# ornamentOrbV1.net
KiCad netlist of a schematic drawn in EAGLE
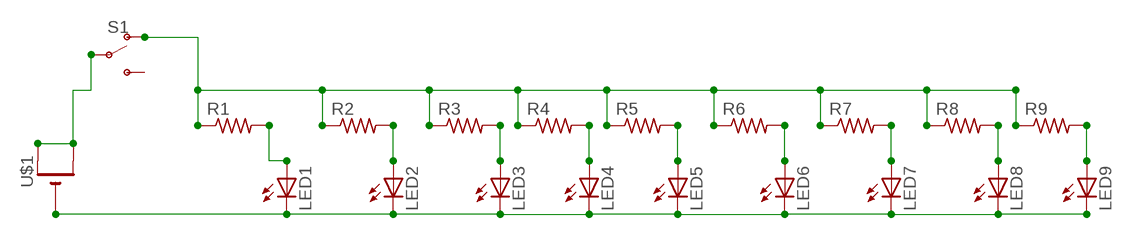
[diagram p0: schematic, sheet 1]

(export (version "E")
  (design (tool "Eeschema 10.0.6"))
  (components
    (comp (ref "LED1")
      (value "LED5MM")
      (footprint "eagle-import:LED5MM")
      (libsource (lib "eagle-import") (part "LED5MM"))
    )
    (comp (ref "LED2")
      (value "LED5MM")
      (footprint "eagle-import:LED5MM")
      (libsource (lib "eagle-import") (part "LED5MM"))
    )
    (comp (ref "LED3")
      (value "LED5MM")
      (footprint "eagle-import:LED5MM")
      (libsource (lib "eagle-import") (part "LED5MM"))
    )
    (comp (ref "LED4")
      (value "LED5MM")
      (footprint "eagle-import:LED5MM")
      (libsource (lib "eagle-import") (part "LED5MM"))
    )
    (comp (ref "LED5")
      (value "LED5MM")
      (footprint "eagle-import:LED5MM")
      (libsource (lib "eagle-import") (part "LED5MM"))
    )
    (comp (ref "LED6")
      (value "LED5MM")
      (footprint "eagle-import:LED5MM")
      (libsource (lib "eagle-import") (part "LED5MM"))
    )
    (comp (ref "LED7")
      (value "LED5MM")
      (footprint "eagle-import:LED5MM")
      (libsource (lib "eagle-import") (part "LED5MM"))
    )
    (comp (ref "LED8")
      (value "LED5MM")
      (footprint "eagle-import:LED5MM")
      (libsource (lib "eagle-import") (part "LED5MM"))
    )
    (comp (ref "LED9")
      (value "LED5MM")
      (footprint "eagle-import:LED5MM")
      (libsource (lib "eagle-import") (part "LED5MM"))
    )
    (comp (ref "R1")
      (value "R-US_R0805")
      (footprint "eagle-import:R0805")
      (libsource (lib "eagle-import") (part "R-US_R0805"))
    )
    (comp (ref "R2")
      (value "R-US_R0805")
      (footprint "eagle-import:R0805")
      (libsource (lib "eagle-import") (part "R-US_R0805"))
    )
    (comp (ref "R3")
      (value "R-US_R0805")
      (footprint "eagle-import:R0805")
      (libsource (lib "eagle-import") (part "R-US_R0805"))
    )
    (comp (ref "R4")
      (value "R-US_R0805")
      (footprint "eagle-import:R0805")
      (libsource (lib "eagle-import") (part "R-US_R0805"))
    )
    (comp (ref "R5")
      (value "R-US_R0805")
      (footprint "eagle-import:R0805")
      (libsource (lib "eagle-import") (part "R-US_R0805"))
    )
    (comp (ref "R6")
      (value "R-US_R0805")
      (footprint "eagle-import:R0805")
      (libsource (lib "eagle-import") (part "R-US_R0805"))
    )
    (comp (ref "R7")
      (value "R-US_R0805")
      (footprint "eagle-import:R0805")
      (libsource (lib "eagle-import") (part "R-US_R0805"))
    )
    (comp (ref "R8")
      (value "R-US_R0805")
      (footprint "eagle-import:R0805")
      (libsource (lib "eagle-import") (part "R-US_R0805"))
    )
    (comp (ref "R9")
      (value "R-US_R0805")
      (footprint "eagle-import:R0805")
      (libsource (lib "eagle-import") (part "R-US_R0805"))
    )
    (comp (ref "S1")
      (value "SWITCH-SPDT-SMD-RIGHT-ANGLE")
      (footprint "eagle-import:SWITCH_SPST_SMD_A")
      (libsource (lib "eagle-import") (part "SWITCH-SPDT-SMD-RIGHT-ANGLE"))
    )
    (comp (ref "U$1")
      (value "CR2032SMT")
      (footprint "eagle-import:CR2032-SMD")
      (libsource (lib "eagle-import") (part "CR2032SMT"))
    )
  )
  (nets
    (net (code "1") (name "Net-(LED1-C)") (class "Default")
      (node (ref "LED1") (pin "K") (pinfunction "C_K") (pintype "passive"))
      (node (ref "LED2") (pin "K") (pinfunction "C_K") (pintype "passive"))
      (node (ref "LED3") (pin "K") (pinfunction "C_K") (pintype "passive"))
      (node (ref "LED4") (pin "K") (pinfunction "C_K") (pintype "passive"))
      (node (ref "LED5") (pin "K") (pinfunction "C_K") (pintype "passive"))
      (node (ref "LED6") (pin "K") (pinfunction "C_K") (pintype "passive"))
      (node (ref "LED7") (pin "K") (pinfunction "C_K") (pintype "passive"))
      (node (ref "LED8") (pin "K") (pinfunction "C_K") (pintype "passive"))
      (node (ref "LED9") (pin "K") (pinfunction "C_K") (pintype "passive"))
      (node (ref "U$1") (pin "-") (pinfunction "-_-") (pintype "passive"))
    )
    (net (code "2") (name "Net-(LED1-PadA)") (class "Default")
      (node (ref "LED1") (pin "A") (pinfunction "A_A") (pintype "passive"))
      (node (ref "R1") (pin "2") (pinfunction "2_2") (pintype "passive"))
    )
    (net (code "3") (name "Net-(LED2-PadA)") (class "Default")
      (node (ref "LED2") (pin "A") (pinfunction "A_A") (pintype "passive"))
      (node (ref "R2") (pin "2") (pinfunction "2_2") (pintype "passive"))
    )
    (net (code "4") (name "Net-(LED3-PadA)") (class "Default")
      (node (ref "LED3") (pin "A") (pinfunction "A_A") (pintype "passive"))
      (node (ref "R3") (pin "2") (pinfunction "2_2") (pintype "passive"))
    )
    (net (code "5") (name "Net-(LED4-PadA)") (class "Default")
      (node (ref "LED4") (pin "A") (pinfunction "A_A") (pintype "passive"))
      (node (ref "R4") (pin "2") (pinfunction "2_2") (pintype "passive"))
    )
    (net (code "6") (name "Net-(LED5-PadA)") (class "Default")
      (node (ref "LED5") (pin "A") (pinfunction "A_A") (pintype "passive"))
      (node (ref "R5") (pin "2") (pinfunction "2_2") (pintype "passive"))
    )
    (net (code "7") (name "Net-(LED6-PadA)") (class "Default")
      (node (ref "LED6") (pin "A") (pinfunction "A_A") (pintype "passive"))
      (node (ref "R6") (pin "2") (pinfunction "2_2") (pintype "passive"))
    )
    (net (code "8") (name "Net-(LED7-PadA)") (class "Default")
      (node (ref "LED7") (pin "A") (pinfunction "A_A") (pintype "passive"))
      (node (ref "R7") (pin "2") (pinfunction "2_2") (pintype "passive"))
    )
    (net (code "9") (name "Net-(LED8-PadA)") (class "Default")
      (node (ref "LED8") (pin "A") (pinfunction "A_A") (pintype "passive"))
      (node (ref "R8") (pin "2") (pinfunction "2_2") (pintype "passive"))
    )
    (net (code "10") (name "Net-(LED9-PadA)") (class "Default")
      (node (ref "LED9") (pin "A") (pinfunction "A_A") (pintype "passive"))
      (node (ref "R9") (pin "2") (pinfunction "2_2") (pintype "passive"))
    )
    (net (code "11") (name "Net-(S1-O)") (class "Default")
      (node (ref "R1") (pin "1") (pinfunction "1_1") (pintype "passive"))
      (node (ref "R2") (pin "1") (pinfunction "1_1") (pintype "passive"))
      (node (ref "R3") (pin "1") (pinfunction "1_1") (pintype "passive"))
      (node (ref "R4") (pin "1") (pinfunction "1_1") (pintype "passive"))
      (node (ref "R5") (pin "1") (pinfunction "1_1") (pintype "passive"))
      (node (ref "R6") (pin "1") (pinfunction "1_1") (pintype "passive"))
      (node (ref "R7") (pin "1") (pinfunction "1_1") (pintype "passive"))
      (node (ref "R8") (pin "1") (pinfunction "1_1") (pintype "passive"))
      (node (ref "R9") (pin "1") (pinfunction "1_1") (pintype "passive"))
      (node (ref "S1") (pin "1") (pinfunction "O_1") (pintype "passive"))
    )
    (net (code "12") (name "Net-(S1-P)") (class "Default")
      (node (ref "S1") (pin "2") (pinfunction "P_2") (pintype "passive"))
      (node (ref "U$1") (pin "+$1") (pinfunction "+_+$1") (pintype "passive"))
      (node (ref "U$1") (pin "+$2") (pinfunction "+1_+$2") (pintype "passive"))
    )
    (net (code "13") (name "unconnected-(S1-S-Pad3)") (class "Default")
      (node (ref "S1") (pin "3") (pinfunction "S_3") (pintype "passive"))
    )
  )
)
